# DC-DC_5V0_To_24V_TPS61175PWPR.net
KiCad netlist of a schematic drawn in Altium Designer
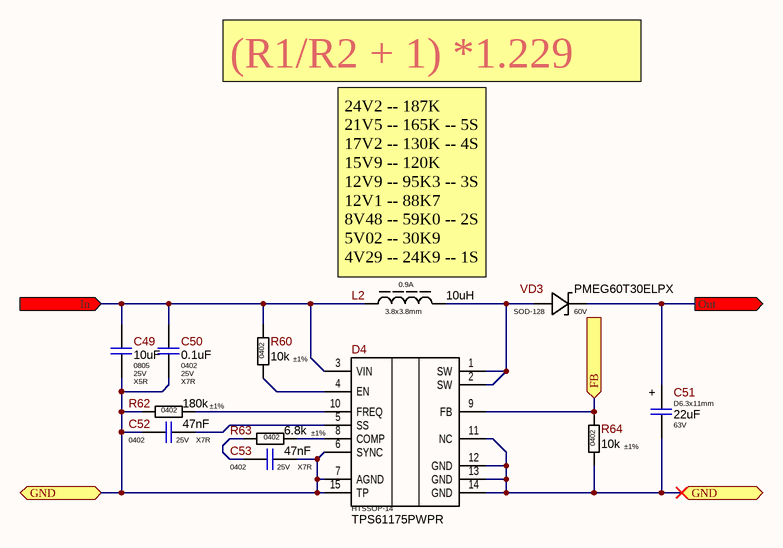
[diagram p0: DC-DC_5V0_To_24V_TPS61175PWPR.SchDoc]

(export (version "E")
  (design (tool "Eeschema 10.0.6"))
  (components
    (comp (ref "C49")
      (value "10uF")
      (footprint "CAP-0805(2012)X85T10")
      (description "10uF 25V X5R ±20% 0805 Ceramic Capacitor RoHS")
      (fields
        (field (name "PACKAGE") "0805")
        (field (name "VOLTAGE") "25V")
        (field (name "DIELECTRIC TYPE") "X5R")
        (field (name "PART NUMBER") "C2012X5R1E106M085AC")
        (field (name "MANUFACTURER") "TDK Corporation")
      )
      (libsource (lib "EL.XXX.T01") (part "Capacitor-NonPolar"))
    )
    (comp (ref "C50")
      (value "0.1uF")
      (footprint "C_CERAMIC_0402_MED")
      (description "100nF 25V X7R ±10% 0402 Ceramic Capacitor RoHS")
      (fields
        (field (name "PACKAGE") "0402")
        (field (name "VOLTAGE") "25V")
        (field (name "DIELECTRIC TYPE") "X7R")
        (field (name "PART NUMBER") "GRM155R71E104KE14D")
        (field (name "MANUFACTURER") "Murata Electronics")
      )
      (libsource (lib "EL.XXX.T01") (part "Capacitor-NonPolar"))
    )
    (comp (ref "C51")
      (value "22uF")
      (footprint "CAP-AE-PTH-63D05x110H15")
      (description "22uF 63V ±20% D6.3x11mm Aluminum Electrolytic Capacitor, Ripple Current 170mA")
      (fields
        (field (name "PACKAGE") "D6.3x11mm")
        (field (name "VOLTAGE") "63V")
        (field (name "PART NUMBER") "ULD1J220MED")
        (field (name "MANUFACTURER") "Nichicon")
      )
      (libsource (lib "EL.XXX.T01") (part "Capacitor-Polar"))
    )
    (comp (ref "C52")
      (value "47nF")
      (footprint "C_CERAMIC_0402_MED")
      (description "47nF 25V X7R ±10% 0402 Ceramic Capacitor RoHS")
      (fields
        (field (name "PACKAGE") "0402")
        (field (name "VOLTAGE") "25V")
        (field (name "DIELECTRIC TYPE") "X7R")
        (field (name "PART NUMBER") "GRM155R71E473KA88D")
        (field (name "MANUFACTURER") "Murata Electronics")
      )
      (libsource (lib "EL.XXX.T01") (part "Capacitor-NonPolar"))
    )
    (comp (ref "C53")
      (value "47nF")
      (footprint "C_CERAMIC_0402_MED")
      (description "47nF 25V X7R ±10% 0402 Ceramic Capacitor RoHS")
      (fields
        (field (name "PACKAGE") "0402")
        (field (name "VOLTAGE") "25V")
        (field (name "DIELECTRIC TYPE") "X7R")
        (field (name "PART NUMBER") "GRM155R71E473KA88D")
        (field (name "MANUFACTURER") "Murata Electronics")
      )
      (libsource (lib "EL.XXX.T01") (part "Capacitor-NonPolar"))
    )
    (comp (ref "D4")
      (value "TPS61175PWPR")
      (footprint "TSSOP-14_POWER")
      (fields
        (field (name "PACKAGE") "HTSSOP-14")
        (field (name "PART NUMBER") "TPS61175PWPR")
        (field (name "MANUFACTURER") "Texas Instruments")
      )
      (libsource (lib "EL.XXX.T01") (part "TPS61175PWP"))
    )
    (comp (ref "L2")
      (value "10uH")
      (footprint "CDRH3D18")
      (description "10uH Shielded Power Inductor 900mA 205mOhm Max Nonstandard")
      (fields
        (field (name "CURRENT") "0.9A")
        (field (name "PACKAGE") "3.8x3.8mm")
        (field (name "PART NUMBER") "CDRH3D18NP-100NC")
        (field (name "TOLERANCE") "±30%")
      )
      (libsource (lib "EL.XXX.T01") (part "Inductor-Ferrite-Fixed"))
    )
    (comp (ref "R60")
      (value "10k")
      (footprint "R_ANY_CHIP_0402_MED")
      (description "10 kOhms ±1% 1/16W 0402 Thick Film Resistor")
      (fields
        (field (name "TOLERANCE") "±1%")
        (field (name "PACKAGE") "0402")
        (field (name "PART NUMBER") "RC0402FR-0710KL")
        (field (name "MANUFACTURER") "Yageo")
      )
      (libsource (lib "EL.XXX.T01") (part "Resistor"))
    )
    (comp (ref "R62")
      (value "180k")
      (footprint "R_ANY_CHIP_0402_MED")
      (description "180 kOhms ±1% 1/16W 0402 Thick Film Resistor")
      (fields
        (field (name "TOLERANCE") "±1%")
        (field (name "PACKAGE") "0402")
        (field (name "PART NUMBER") "RC0402FR-07180KL")
        (field (name "MANUFACTURER") "Yageo")
      )
      (libsource (lib "EL.XXX.T01") (part "Resistor"))
    )
    (comp (ref "R63")
      (value "6.8k")
      (footprint "R_ANY_CHIP_0402_MED")
      (description "6.8k kOhms ±1%, 1/16W 0402 Thick Film Resistor")
      (fields
        (field (name "TOLERANCE") "±1%")
        (field (name "PACKAGE") "0402")
        (field (name "PART NUMBER") "RC0402FR-076K8L")
        (field (name "MANUFACTURER") "Yageo")
      )
      (libsource (lib "EL.XXX.T01") (part "Resistor"))
    )
    (comp (ref "R64")
      (value "10k")
      (footprint "R_ANY_CHIP_0402_MED")
      (description "10 kOhms ±1% 1/16W 0402 Thick Film Resistor")
      (fields
        (field (name "TOLERANCE") "±1%")
        (field (name "PACKAGE") "0402")
        (field (name "PART NUMBER") "RC0402FR-0710KL")
        (field (name "MANUFACTURER") "Yageo")
      )
      (libsource (lib "EL.XXX.T01") (part "Resistor"))
    )
    (comp (ref "VD3")
      (value "PMEG60T30ELPX")
      (footprint "SOD-128")
      (description "Diode Schottky 60V 3A, 550mV @ 3A, 16ns Recovery Time, SOD-128")
      (fields
        (field (name "PART NUMBER") "PMEG60T30ELPX")
        (field (name "PACKAGE") "SOD-128")
        (field (name "VOLTAGE") "60V")
        (field (name "MANUFACTURER") "Nexperia USA")
      )
      (libsource (lib "EL.XXX.T01") (part "Diode-Schottky"))
    )
  )
  (nets
    (net (code "1") (name "/FB") (class "Default")
      (node (ref "D4") (pin "9") (pinfunction "FB_9") (pintype "passive"))
      (node (ref "R64") (pin "2") (pintype "passive"))
    )
    (net (code "2") (name "/GND") (class "Default")
      (node (ref "C49") (pin "2") (pinfunction "2_2") (pintype "passive"))
      (node (ref "C50") (pin "2") (pinfunction "2_2") (pintype "passive"))
      (node (ref "C51") (pin "2") (pinfunction "2_2") (pintype "passive"))
      (node (ref "C52") (pin "1") (pinfunction "1_1") (pintype "passive"))
      (node (ref "C53") (pin "2") (pinfunction "2_2") (pintype "passive"))
      (node (ref "D4") (pin "11") (pinfunction "NC_11") (pintype "passive"))
      (node (ref "D4") (pin "12") (pinfunction "GND_12") (pintype "passive"))
      (node (ref "D4") (pin "13") (pinfunction "GND_13") (pintype "passive"))
      (node (ref "D4") (pin "14") (pinfunction "GND_14") (pintype "passive"))
      (node (ref "D4") (pin "15") (pinfunction "TP_15") (pintype "passive"))
      (node (ref "D4") (pin "6") (pinfunction "SYNC_6") (pintype "passive"))
      (node (ref "D4") (pin "7") (pinfunction "AGND_7") (pintype "passive"))
      (node (ref "R62") (pin "1") (pintype "passive"))
      (node (ref "R64") (pin "1") (pintype "passive"))
    )
    (net (code "3") (name "/In") (class "Default")
      (node (ref "C49") (pin "1") (pinfunction "1_1") (pintype "passive"))
      (node (ref "C50") (pin "1") (pinfunction "1_1") (pintype "passive"))
      (node (ref "D4") (pin "3") (pinfunction "VIN_3") (pintype "passive"))
      (node (ref "L2") (pin "1") (pintype "passive"))
      (node (ref "R60") (pin "2") (pintype "passive"))
    )
    (net (code "4") (name "/Out") (class "Default")
      (node (ref "C51") (pin "1") (pinfunction "1_1") (pintype "passive"))
      (node (ref "VD3") (pin "CA") (pintype "passive"))
    )
    (net (code "5") (name "Net-(C53-Pad1)") (class "Default")
      (node (ref "C53") (pin "1") (pinfunction "1_1") (pintype "passive"))
      (node (ref "R63") (pin "2") (pintype "passive"))
    )
    (net (code "6") (name "Net-(D4-COMP)") (class "Default")
      (node (ref "D4") (pin "8") (pinfunction "COMP_8") (pintype "passive"))
      (node (ref "R63") (pin "1") (pintype "passive"))
    )
    (net (code "7") (name "Net-(D4-EN)") (class "Default")
      (node (ref "D4") (pin "4") (pinfunction "EN_4") (pintype "passive"))
      (node (ref "R60") (pin "1") (pintype "passive"))
    )
    (net (code "8") (name "Net-(D4-FREQ)") (class "Default")
      (node (ref "D4") (pin "10") (pinfunction "FREQ_10") (pintype "passive"))
      (node (ref "R62") (pin "2") (pintype "passive"))
    )
    (net (code "9") (name "Net-(D4-SS)") (class "Default")
      (node (ref "C52") (pin "2") (pinfunction "2_2") (pintype "passive"))
      (node (ref "D4") (pin "5") (pinfunction "SS_5") (pintype "passive"))
    )
    (net (code "10") (name "Net-(D4-SW-Pad1)") (class "Default")
      (node (ref "D4") (pin "1") (pinfunction "SW_1") (pintype "passive"))
      (node (ref "D4") (pin "2") (pinfunction "SW_2") (pintype "passive"))
      (node (ref "L2") (pin "2") (pintype "passive"))
      (node (ref "VD3") (pin "AN") (pintype "passive"))
    )
  )
)
